# supply.net
KiCad netlist of a schematic drawn in EAGLE
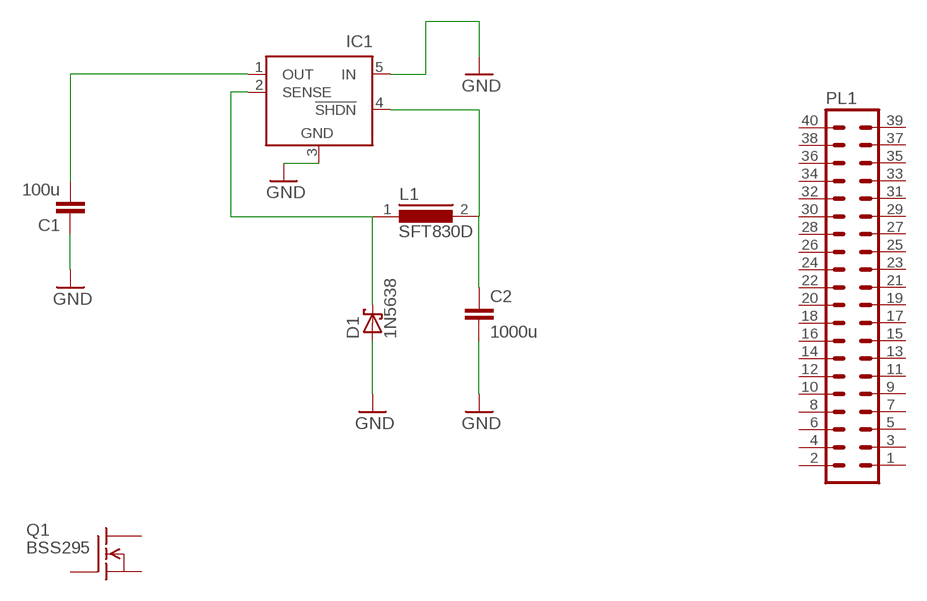
[diagram p0: schematic, sheet 1]

(export (version "E")
  (design (tool "Eeschema 10.0.6"))
  (components
    (comp (ref "C1")
      (value "100u")
      (footprint "eagle-import:C2.5-3")
      (libsource (lib "eagle-import") (part "C2,5-3"))
    )
    (comp (ref "C2")
      (value "1000u")
      (footprint "eagle-import:C2.5-3")
      (libsource (lib "eagle-import") (part "C2,5-3"))
    )
    (comp (ref "D1")
      (value "1N5638")
      (footprint "eagle-import:DO13M")
      (libsource (lib "eagle-import") (part "1N5638"))
    )
    (comp (ref "IC1")
      (value "LT1129CT-5")
      (footprint "eagle-import:TO220-5")
      (fields (field (name "MPN") "LT1129CT-5#PBF"))
      (libsource (lib "eagle-import") (part "LT1129CT-5"))
    )
    (comp (ref "L1")
      (value "SFT830D")
      (footprint "eagle-import:SFT830D")
      (libsource (lib "eagle-import") (part "SFT830D"))
    )
    (comp (ref "PL1")
      (value "40V")
      (footprint "eagle-import:40V")
      (libsource (lib "eagle-import") (part "40V"))
    )
    (comp (ref "Q1")
      (value "BSS295")
      (footprint "eagle-import:TO92")
      (libsource (lib "eagle-import") (part "BSS295"))
    )
  )
  (nets
    (net (code "1") (name "GND") (class "Default")
      (node (ref "C1") (pin "1") (pinfunction "1_1") (pintype "passive"))
      (node (ref "C2") (pin "2") (pinfunction "2_2") (pintype "passive"))
      (node (ref "D1") (pin "A") (pinfunction "A_A") (pintype "passive"))
      (node (ref "IC1") (pin "3") (pinfunction "GND_3") (pintype "power_in"))
      (node (ref "IC1") (pin "5") (pinfunction "IN_5") (pintype "input"))
    )
    (net (code "2") (name "Net-(IC1-OUT)") (class "Default")
      (node (ref "C1") (pin "2") (pinfunction "2_2") (pintype "passive"))
      (node (ref "IC1") (pin "1") (pinfunction "OUT_1") (pintype "output"))
    )
    (net (code "3") (name "Net-(IC1-SENSE)") (class "Default")
      (node (ref "D1") (pin "C") (pinfunction "C_C") (pintype "passive"))
      (node (ref "IC1") (pin "2") (pinfunction "SENSE_2") (pintype "input"))
      (node (ref "L1") (pin "1") (pinfunction "1_1") (pintype "passive"))
    )
    (net (code "4") (name "Net-(IC1-~{SHDN})") (class "Default")
      (node (ref "C2") (pin "1") (pinfunction "1_1") (pintype "passive"))
      (node (ref "IC1") (pin "4") (pinfunction "~{SHDN}_4") (pintype "input"))
      (node (ref "L1") (pin "2") (pinfunction "2_2") (pintype "passive"))
    )
    (net (code "5") (name "unconnected-(PL1-Pad1)") (class "Default")
      (node (ref "PL1") (pin "1") (pinfunction "1_1") (pintype "passive"))
    )
    (net (code "6") (name "unconnected-(PL1-Pad2)") (class "Default")
      (node (ref "PL1") (pin "2") (pinfunction "2_2") (pintype "passive"))
    )
    (net (code "7") (name "unconnected-(PL1-Pad3)") (class "Default")
      (node (ref "PL1") (pin "3") (pinfunction "3_3") (pintype "passive"))
    )
    (net (code "8") (name "unconnected-(PL1-Pad4)") (class "Default")
      (node (ref "PL1") (pin "4") (pinfunction "4_4") (pintype "passive"))
    )
    (net (code "9") (name "unconnected-(PL1-Pad5)") (class "Default")
      (node (ref "PL1") (pin "5") (pinfunction "5_5") (pintype "passive"))
    )
    (net (code "10") (name "unconnected-(PL1-Pad6)") (class "Default")
      (node (ref "PL1") (pin "6") (pinfunction "6_6") (pintype "passive"))
    )
    (net (code "11") (name "unconnected-(PL1-Pad7)") (class "Default")
      (node (ref "PL1") (pin "7") (pinfunction "7_7") (pintype "passive"))
    )
    (net (code "12") (name "unconnected-(PL1-Pad8)") (class "Default")
      (node (ref "PL1") (pin "8") (pinfunction "8_8") (pintype "passive"))
    )
    (net (code "13") (name "unconnected-(PL1-Pad9)") (class "Default")
      (node (ref "PL1") (pin "9") (pinfunction "9_9") (pintype "passive"))
    )
    (net (code "14") (name "unconnected-(PL1-Pad10)") (class "Default")
      (node (ref "PL1") (pin "10") (pinfunction "10_10") (pintype "passive"))
    )
    (net (code "15") (name "unconnected-(PL1-Pad11)") (class "Default")
      (node (ref "PL1") (pin "11") (pinfunction "11_11") (pintype "passive"))
    )
    (net (code "16") (name "unconnected-(PL1-Pad12)") (class "Default")
      (node (ref "PL1") (pin "12") (pinfunction "12_12") (pintype "passive"))
    )
    (net (code "17") (name "unconnected-(PL1-Pad13)") (class "Default")
      (node (ref "PL1") (pin "13") (pinfunction "13_13") (pintype "passive"))
    )
    (net (code "18") (name "unconnected-(PL1-Pad14)") (class "Default")
      (node (ref "PL1") (pin "14") (pinfunction "14_14") (pintype "passive"))
    )
    (net (code "19") (name "unconnected-(PL1-Pad15)") (class "Default")
      (node (ref "PL1") (pin "15") (pinfunction "15_15") (pintype "passive"))
    )
    (net (code "20") (name "unconnected-(PL1-Pad16)") (class "Default")
      (node (ref "PL1") (pin "16") (pinfunction "16_16") (pintype "passive"))
    )
    (net (code "21") (name "unconnected-(PL1-Pad17)") (class "Default")
      (node (ref "PL1") (pin "17") (pinfunction "17_17") (pintype "passive"))
    )
    (net (code "22") (name "unconnected-(PL1-Pad18)") (class "Default")
      (node (ref "PL1") (pin "18") (pinfunction "18_18") (pintype "passive"))
    )
    (net (code "23") (name "unconnected-(PL1-Pad19)") (class "Default")
      (node (ref "PL1") (pin "19") (pinfunction "19_19") (pintype "passive"))
    )
    (net (code "24") (name "unconnected-(PL1-Pad20)") (class "Default")
      (node (ref "PL1") (pin "20") (pinfunction "20_20") (pintype "passive"))
    )
    (net (code "25") (name "unconnected-(PL1-Pad21)") (class "Default")
      (node (ref "PL1") (pin "21") (pinfunction "21_21") (pintype "passive"))
    )
    (net (code "26") (name "unconnected-(PL1-Pad22)") (class "Default")
      (node (ref "PL1") (pin "22") (pinfunction "22_22") (pintype "passive"))
    )
    (net (code "27") (name "unconnected-(PL1-Pad23)") (class "Default")
      (node (ref "PL1") (pin "23") (pinfunction "23_23") (pintype "passive"))
    )
    (net (code "28") (name "unconnected-(PL1-Pad24)") (class "Default")
      (node (ref "PL1") (pin "24") (pinfunction "24_24") (pintype "passive"))
    )
    (net (code "29") (name "unconnected-(PL1-Pad25)") (class "Default")
      (node (ref "PL1") (pin "25") (pinfunction "25_25") (pintype "passive"))
    )
    (net (code "30") (name "unconnected-(PL1-Pad26)") (class "Default")
      (node (ref "PL1") (pin "26") (pinfunction "26_26") (pintype "passive"))
    )
    (net (code "31") (name "unconnected-(PL1-Pad27)") (class "Default")
      (node (ref "PL1") (pin "27") (pinfunction "27_27") (pintype "passive"))
    )
    (net (code "32") (name "unconnected-(PL1-Pad28)") (class "Default")
      (node (ref "PL1") (pin "28") (pinfunction "28_28") (pintype "passive"))
    )
    (net (code "33") (name "unconnected-(PL1-Pad29)") (class "Default")
      (node (ref "PL1") (pin "29") (pinfunction "29_29") (pintype "passive"))
    )
    (net (code "34") (name "unconnected-(PL1-Pad30)") (class "Default")
      (node (ref "PL1") (pin "30") (pinfunction "30_30") (pintype "passive"))
    )
    (net (code "35") (name "unconnected-(PL1-Pad31)") (class "Default")
      (node (ref "PL1") (pin "31") (pinfunction "31_31") (pintype "passive"))
    )
    (net (code "36") (name "unconnected-(PL1-Pad32)") (class "Default")
      (node (ref "PL1") (pin "32") (pinfunction "32_32") (pintype "passive"))
    )
    (net (code "37") (name "unconnected-(PL1-Pad33)") (class "Default")
      (node (ref "PL1") (pin "33") (pinfunction "33_33") (pintype "passive"))
    )
    (net (code "38") (name "unconnected-(PL1-Pad34)") (class "Default")
      (node (ref "PL1") (pin "34") (pinfunction "34_34") (pintype "passive"))
    )
    (net (code "39") (name "unconnected-(PL1-Pad35)") (class "Default")
      (node (ref "PL1") (pin "35") (pinfunction "35_35") (pintype "passive"))
    )
    (net (code "40") (name "unconnected-(PL1-Pad36)") (class "Default")
      (node (ref "PL1") (pin "36") (pinfunction "36_36") (pintype "passive"))
    )
    (net (code "41") (name "unconnected-(PL1-Pad37)") (class "Default")
      (node (ref "PL1") (pin "37") (pinfunction "37_37") (pintype "passive"))
    )
    (net (code "42") (name "unconnected-(PL1-Pad38)") (class "Default")
      (node (ref "PL1") (pin "38") (pinfunction "38_38") (pintype "passive"))
    )
    (net (code "43") (name "unconnected-(PL1-Pad39)") (class "Default")
      (node (ref "PL1") (pin "39") (pinfunction "39_39") (pintype "passive"))
    )
    (net (code "44") (name "unconnected-(PL1-Pad40)") (class "Default")
      (node (ref "PL1") (pin "40") (pinfunction "40_40") (pintype "passive"))
    )
    (net (code "45") (name "unconnected-(Q1-D-Pad2)") (class "Default")
      (node (ref "Q1") (pin "2") (pinfunction "D_2") (pintype "passive"))
    )
    (net (code "46") (name "unconnected-(Q1-G-Pad1)") (class "Default")
      (node (ref "Q1") (pin "1") (pinfunction "G_1") (pintype "passive"))
    )
    (net (code "47") (name "unconnected-(Q1-S-Pad3)") (class "Default")
      (node (ref "Q1") (pin "3") (pinfunction "S_3") (pintype "passive"))
    )
  )
)
